# JouleThief-PCBCOIL.net
KiCad netlist of a schematic drawn in EAGLE
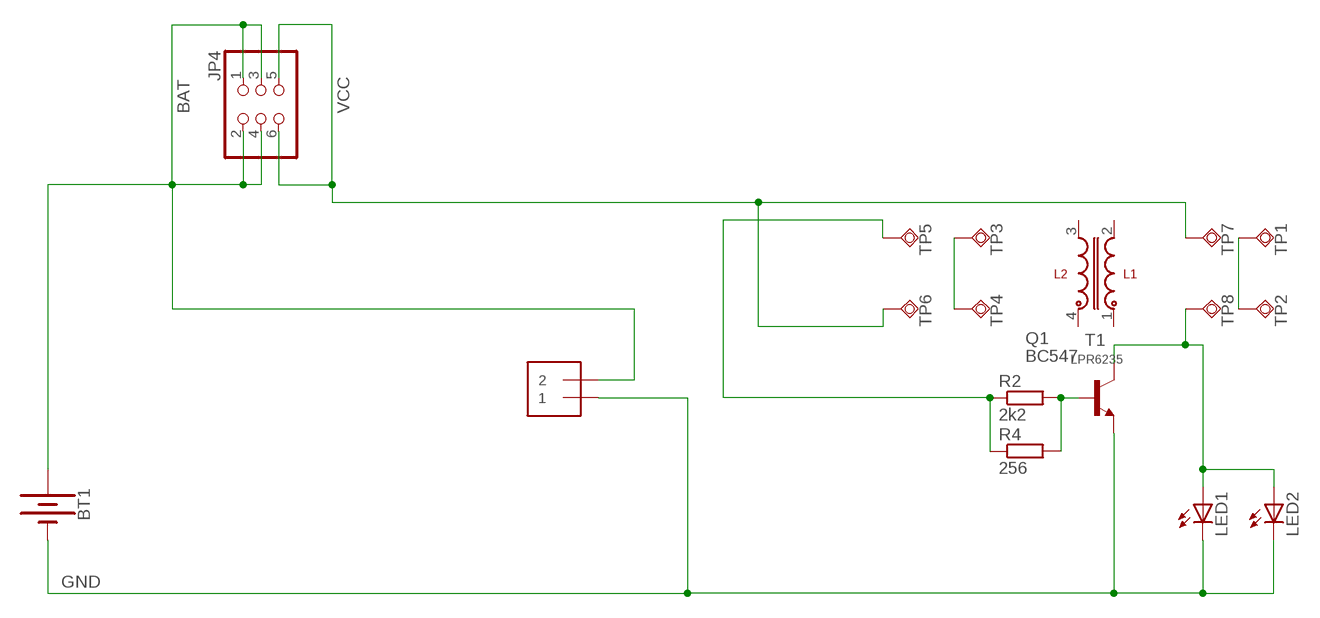
[diagram p0: schematic, sheet 1]

(export (version "E")
  (design (tool "Eeschema 10.0.6"))
  (components
    (comp (ref "BT1")
      (value "BATTERY-AAA_KIT")
      (footprint "eagle-import:BATTERY-AAA-KIT")
      (libsource (lib "eagle-import") (part "BATTERY-AAA_KIT"))
    )
    (comp (ref "J1")
      (value "1X2-3.5MM")
      (footprint "eagle-import:1X2-3.5MM")
      (libsource (lib "eagle-import") (part "1X2-3.5MM"))
    )
    (comp (ref "JP4")
      (value "PINHD-2X3")
      (footprint "eagle-import:2X03")
      (libsource (lib "eagle-import") (part "PINHD-2X3"))
    )
    (comp (ref "LED1")
      (value "LEDKA-3528ASYC")
      (footprint "eagle-import:KA-3528ASYC")
      (libsource (lib "eagle-import") (part "LEDKA-3528ASYC"))
    )
    (comp (ref "LED2")
      (value "LED5MM")
      (footprint "eagle-import:LED5MM")
      (libsource (lib "eagle-import") (part "LED5MM"))
    )
    (comp (ref "Q1")
      (value "BC547")
      (footprint "eagle-import:TO92")
      (libsource (lib "eagle-import") (part "BC547"))
    )
    (comp (ref "R2")
      (value "2k2")
      (footprint "eagle-import:0204_5@1")
      (libsource (lib "eagle-import") (part "R-EU_0204/5"))
    )
    (comp (ref "R4")
      (value "256")
      (footprint "eagle-import:R0603")
      (libsource (lib "eagle-import") (part "resistor_R-EU_R0603"))
    )
    (comp (ref "T1")
      (value "LPR6235")
      (footprint "eagle-import:LPR6235")
      (libsource (lib "eagle-import") (part "LPR6235"))
    )
    (comp (ref "TP1")
      (value "TPSQTP07R")
      (footprint "eagle-import:TP07R")
      (libsource (lib "eagle-import") (part "TPSQTP07R"))
    )
    (comp (ref "TP2")
      (value "TPSQTP07R")
      (footprint "eagle-import:TP07R")
      (libsource (lib "eagle-import") (part "TPSQTP07R"))
    )
    (comp (ref "TP3")
      (value "TPSQTP07R")
      (footprint "eagle-import:TP07R")
      (libsource (lib "eagle-import") (part "TPSQTP07R"))
    )
    (comp (ref "TP4")
      (value "TPSQTP07R")
      (footprint "eagle-import:TP07R")
      (libsource (lib "eagle-import") (part "TPSQTP07R"))
    )
    (comp (ref "TP5")
      (value "TPSQTP07R")
      (footprint "eagle-import:TP07R")
      (libsource (lib "eagle-import") (part "TPSQTP07R"))
    )
    (comp (ref "TP6")
      (value "TPSQTP07R")
      (footprint "eagle-import:TP07R")
      (libsource (lib "eagle-import") (part "TPSQTP07R"))
    )
    (comp (ref "TP7")
      (value "TPSQTP07R")
      (footprint "eagle-import:TP07R")
      (libsource (lib "eagle-import") (part "TPSQTP07R"))
    )
    (comp (ref "TP8")
      (value "TPSQTP07R")
      (footprint "eagle-import:TP07R")
      (libsource (lib "eagle-import") (part "TPSQTP07R"))
    )
  )
  (nets
    (net (code "1") (name "/BAT") (class "Default")
      (node (ref "BT1") (pin "PWR@1") (pinfunction "+_PWR@1") (pintype "power_in"))
      (node (ref "J1") (pin "2") (pinfunction "2_2") (pintype "passive"))
      (node (ref "JP4") (pin "1") (pinfunction "1_1") (pintype "passive"))
      (node (ref "JP4") (pin "2") (pinfunction "2_2") (pintype "passive"))
      (node (ref "JP4") (pin "3") (pinfunction "3_3") (pintype "passive"))
      (node (ref "JP4") (pin "4") (pinfunction "4_4") (pintype "passive"))
    )
    (net (code "2") (name "/GND") (class "Default")
      (node (ref "BT1") (pin "GND@1") (pinfunction "-_GND@1") (pintype "power_in"))
      (node (ref "J1") (pin "1") (pinfunction "1_1") (pintype "passive"))
      (node (ref "LED1") (pin "C") (pinfunction "C_C") (pintype "passive"))
      (node (ref "LED2") (pin "K") (pinfunction "C_K") (pintype "passive"))
      (node (ref "Q1") (pin "1") (pinfunction "E_1") (pintype "passive"))
    )
    (net (code "3") (name "/VCC") (class "Default")
      (node (ref "JP4") (pin "5") (pinfunction "5_5") (pintype "passive"))
      (node (ref "JP4") (pin "6") (pinfunction "6_6") (pintype "passive"))
      (node (ref "TP6") (pin "TP") (pinfunction "TP_TP") (pintype "input"))
      (node (ref "TP7") (pin "TP") (pinfunction "TP_TP") (pintype "input"))
    )
    (net (code "4") (name "Net-(Q1-B)") (class "Default")
      (node (ref "Q1") (pin "2") (pinfunction "B_2") (pintype "passive"))
      (node (ref "R2") (pin "2") (pinfunction "2_2") (pintype "passive"))
      (node (ref "R4") (pin "2") (pinfunction "2_2") (pintype "passive"))
    )
    (net (code "5") (name "Net-(Q1-C)") (class "Default")
      (node (ref "LED1") (pin "A") (pinfunction "A_A") (pintype "passive"))
      (node (ref "LED2") (pin "A") (pinfunction "A_A") (pintype "passive"))
      (node (ref "Q1") (pin "3") (pinfunction "C_3") (pintype "passive"))
      (node (ref "TP8") (pin "TP") (pinfunction "TP_TP") (pintype "input"))
    )
    (net (code "6") (name "Net-(R2-Pad1)") (class "Default")
      (node (ref "R2") (pin "1") (pinfunction "1_1") (pintype "passive"))
      (node (ref "R4") (pin "1") (pinfunction "1_1") (pintype "passive"))
      (node (ref "TP5") (pin "TP") (pinfunction "TP_TP") (pintype "input"))
    )
    (net (code "7") (name "Net-(TP1-PadTP)") (class "Default")
      (node (ref "TP1") (pin "TP") (pinfunction "TP_TP") (pintype "input"))
      (node (ref "TP2") (pin "TP") (pinfunction "TP_TP") (pintype "input"))
    )
    (net (code "8") (name "Net-(TP3-PadTP)") (class "Default")
      (node (ref "TP3") (pin "TP") (pinfunction "TP_TP") (pintype "input"))
      (node (ref "TP4") (pin "TP") (pinfunction "TP_TP") (pintype "input"))
    )
    (net (code "9") (name "unconnected-(T1-Pad1)") (class "Default")
      (node (ref "T1") (pin "1") (pinfunction "1_1") (pintype "bidirectional"))
    )
    (net (code "10") (name "unconnected-(T1-Pad2)") (class "Default")
      (node (ref "T1") (pin "2") (pinfunction "2_2") (pintype "bidirectional"))
    )
    (net (code "11") (name "unconnected-(T1-Pad3)") (class "Default")
      (node (ref "T1") (pin "3") (pinfunction "3_3") (pintype "bidirectional"))
    )
    (net (code "12") (name "unconnected-(T1-Pad4)") (class "Default")
      (node (ref "T1") (pin "4") (pinfunction "4_4") (pintype "bidirectional"))
    )
  )
)
